# POWER2.net
KiCad netlist of a schematic drawn in Altium Designer
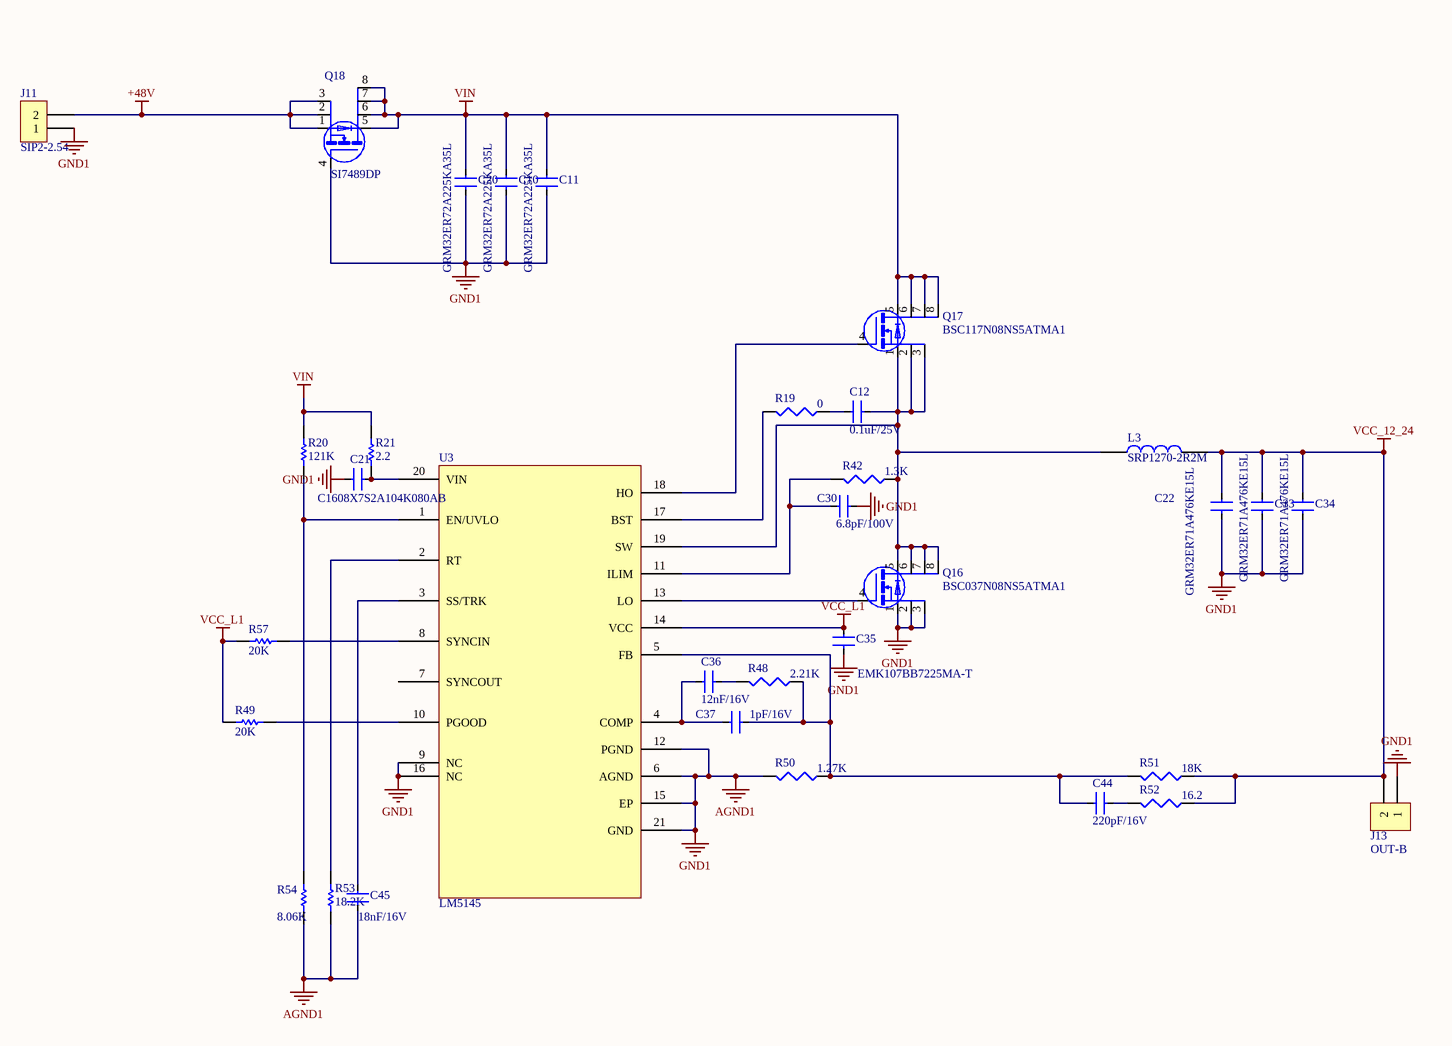
[diagram p0: POWER2.SchDoc]

(export (version "E")
  (design (tool "Eeschema 10.0.6"))
  (components
    (comp (ref "C10")
      (value "GRM32ER72A225KA35L")
      (footprint "1210C")
      (description "CCX85-103")
      (libsource (lib "无极性电容") (part "0.01UF"))
    )
    (comp (ref "C11")
      (value "GRM32ER72A225KA35L")
      (footprint "1210C")
      (description "CCX85-103")
      (libsource (lib "无极性电容") (part "0.01UF"))
    )
    (comp (ref "C12")
      (value "0.1uF/25V")
      (footprint "0603C")
      (description "CCX85-103")
      (libsource (lib "无极性电容") (part "0.01UF"))
    )
    (comp (ref "C20")
      (value "GRM32ER72A225KA35L")
      (footprint "1210C")
      (description "CCX85-103")
      (libsource (lib "无极性电容") (part "0.01UF"))
    )
    (comp (ref "C21")
      (value "C1608X7S2A104K080AB")
      (footprint "0603C")
      (description "CCX85-103")
      (libsource (lib "无极性电容") (part "0.01UF"))
    )
    (comp (ref "C22")
      (value "GRM32ER71A476KE15L")
      (footprint "1210C")
      (description "CCX85-103")
      (libsource (lib "无极性电容") (part "0.01UF"))
    )
    (comp (ref "C30")
      (value "6.8pF/100V")
      (footprint "0603C")
      (description "CCX85-103")
      (libsource (lib "无极性电容") (part "0.01UF"))
    )
    (comp (ref "C33")
      (value "GRM32ER71A476KE15L")
      (footprint "1210C")
      (description "CCX85-103")
      (libsource (lib "无极性电容") (part "0.01UF"))
    )
    (comp (ref "C34")
      (value "GRM32ER71A476KE15L")
      (footprint "1210C")
      (description "CCX85-103")
      (libsource (lib "无极性电容") (part "0.01UF"))
    )
    (comp (ref "C35")
      (value "EMK107BB7225MA-T")
      (footprint "0603C")
      (description "CCX85-103")
      (libsource (lib "无极性电容") (part "0.01UF"))
    )
    (comp (ref "C36")
      (value "12nF/16V")
      (footprint "0603C")
      (description "CCX85-103")
      (libsource (lib "无极性电容") (part "0.01UF"))
    )
    (comp (ref "C37")
      (value "1pF/16V")
      (footprint "0603C")
      (description "CCX85-103")
      (libsource (lib "无极性电容") (part "0.01UF"))
    )
    (comp (ref "C44")
      (value "220pF/16V")
      (footprint "0603C")
      (description "CCX85-103")
      (libsource (lib "无极性电容") (part "0.01UF"))
    )
    (comp (ref "C45")
      (value "18nF/16V")
      (footprint "0603C")
      (description "CCX85-103")
      (libsource (lib "无极性电容") (part "0.01UF"))
    )
    (comp (ref "J11")
      (value "SIP2-2.54")
      (footprint "CH3.96-2P")
      (description "CN-SIP2-2.54")
      (libsource (lib "接插件") (part "SIP2-2.54"))
    )
    (comp (ref "J13")
      (value "OUT-B")
      (footprint "CH3.96-2P")
      (description "Connector")
      (libsource (lib "SM") (part "CON2"))
    )
    (comp (ref "L3")
      (value "SRP1270-2R2M")
      (footprint "SRP1270-2R2M")
      (libsource (lib "*") (part "INDUCTOR"))
    )
    (comp (ref "Q16")
      (value "BSC037N08NS5ATMA1")
      (footprint "PowerPAK SO-8")
      (description "Si4004DY")
      (libsource (lib "Schlib_20110825") (part "Si4004DY"))
    )
    (comp (ref "Q17")
      (value "BSC117N08NS5ATMA1")
      (footprint "PowerPAK SO-8")
      (description "Si4004DY")
      (libsource (lib "Schlib_20110825") (part "Si4004DY"))
    )
    (comp (ref "Q18")
      (value "SI7489DP")
      (footprint "PowerPAK SO-8")
      (description "Si4004DY")
      (libsource (lib "") (part "Si4004DY_1"))
    )
    (comp (ref "R19")
      (value "0")
      (footprint "0603R")
      (description "Resistor")
      (fields (field (name "PUBLISHER") "Altium Limited"))
      (libsource (lib "SM") (part "Res3"))
    )
    (comp (ref "R20")
      (value "121K")
      (footprint "0805R")
      (description "Semiconductor Resistor")
      (fields (field (name "PUBLISHER") "Altium Limited"))
      (libsource (lib "Miscellaneous Devices") (part "Res Semi"))
    )
    (comp (ref "R21")
      (value "2.2")
      (footprint "0603R")
      (description "Semiconductor Resistor")
      (fields (field (name "PUBLISHER") "Altium Limited"))
      (libsource (lib "Miscellaneous Devices") (part "Res Semi"))
    )
    (comp (ref "R42")
      (value "1.3K")
      (footprint "0603R")
      (description "Resistor")
      (fields (field (name "PUBLISHER") "Altium Limited"))
      (libsource (lib "SM") (part "Res3"))
    )
    (comp (ref "R48")
      (value "2.21K")
      (footprint "0603R")
      (description "Resistor")
      (fields (field (name "PUBLISHER") "Altium Limited"))
      (libsource (lib "SM") (part "Res3"))
    )
    (comp (ref "R49")
      (value "20K")
      (footprint "0603R")
      (description "Semiconductor Resistor")
      (fields (field (name "PUBLISHER") "Altium Limited"))
      (libsource (lib "Miscellaneous Devices") (part "Res Semi"))
    )
    (comp (ref "R50")
      (value "1.27K")
      (footprint "0603R")
      (description "Resistor")
      (fields (field (name "PUBLISHER") "Altium Limited"))
      (libsource (lib "SM") (part "Res3"))
    )
    (comp (ref "R51")
      (value "18K")
      (footprint "0603R")
      (description "Resistor")
      (fields (field (name "PUBLISHER") "Altium Limited"))
      (libsource (lib "SM") (part "Res3"))
    )
    (comp (ref "R52")
      (value "16.2")
      (footprint "0603R")
      (description "Resistor")
      (fields (field (name "PUBLISHER") "Altium Limited"))
      (libsource (lib "SM") (part "Res3"))
    )
    (comp (ref "R53")
      (value "18.2K")
      (footprint "0603R")
      (description "Semiconductor Resistor")
      (fields (field (name "PUBLISHER") "Altium Limited"))
      (libsource (lib "Miscellaneous Devices") (part "Res Semi"))
    )
    (comp (ref "R54")
      (value "8.06K")
      (footprint "0603R")
      (description "Semiconductor Resistor")
      (fields (field (name "PUBLISHER") "Altium Limited"))
      (libsource (lib "Miscellaneous Devices") (part "Res Semi"))
    )
    (comp (ref "R57")
      (value "20K")
      (footprint "0603R")
      (description "Semiconductor Resistor")
      (fields (field (name "PUBLISHER") "Altium Limited"))
      (libsource (lib "Miscellaneous Devices") (part "Res Semi"))
    )
    (comp (ref "U3")
      (value "LM5145")
      (footprint "QFN050P600-8N")
      (libsource (lib "Schlib_20110825") (part "LM5145"))
    )
  )
  (nets
    (net (code "1") (name "+48V") (class "Default")
      (node (ref "J11") (pin "2") (pinfunction "2_2") (pintype "passive"))
      (node (ref "Q18") (pin "1") (pinfunction "S_1") (pintype "passive"))
      (node (ref "Q18") (pin "2") (pinfunction "S_2") (pintype "passive"))
      (node (ref "Q18") (pin "3") (pinfunction "S_3") (pintype "passive"))
    )
    (net (code "2") (name "AGND1") (class "Default")
      (node (ref "C10") (pin "2") (pinfunction "2_2") (pintype "passive"))
      (node (ref "C11") (pin "2") (pinfunction "2_2") (pintype "passive"))
      (node (ref "C20") (pin "2") (pinfunction "2_2") (pintype "passive"))
      (node (ref "C21") (pin "1") (pinfunction "1_1") (pintype "passive"))
      (node (ref "C22") (pin "2") (pinfunction "2_2") (pintype "passive"))
      (node (ref "C30") (pin "1") (pinfunction "1_1") (pintype "passive"))
      (node (ref "C33") (pin "2") (pinfunction "2_2") (pintype "passive"))
      (node (ref "C34") (pin "2") (pinfunction "2_2") (pintype "passive"))
      (node (ref "C35") (pin "2") (pinfunction "2_2") (pintype "passive"))
      (node (ref "C45") (pin "2") (pinfunction "2_2") (pintype "passive"))
      (node (ref "J11") (pin "1") (pinfunction "1_1") (pintype "passive"))
      (node (ref "J13") (pin "1") (pinfunction "1_1") (pintype "passive"))
      (node (ref "Q16") (pin "1") (pinfunction "S_1") (pintype "passive"))
      (node (ref "Q16") (pin "2") (pinfunction "S_2") (pintype "passive"))
      (node (ref "Q16") (pin "3") (pinfunction "S_3") (pintype "passive"))
      (node (ref "Q18") (pin "4") (pinfunction "G_4") (pintype "passive"))
      (node (ref "R50") (pin "2") (pinfunction "2_2") (pintype "passive"))
      (node (ref "R53") (pin "1") (pinfunction "1_1") (pintype "passive"))
      (node (ref "R54") (pin "1") (pinfunction "1_1") (pintype "passive"))
      (node (ref "U3") (pin "12") (pinfunction "PGND_12") (pintype "passive"))
      (node (ref "U3") (pin "15") (pinfunction "EP_15") (pintype "passive"))
      (node (ref "U3") (pin "16") (pinfunction "NC_16") (pintype "passive"))
      (node (ref "U3") (pin "21") (pinfunction "GND_21") (pintype "passive"))
      (node (ref "U3") (pin "6") (pinfunction "AGND_6") (pintype "passive"))
      (node (ref "U3") (pin "9") (pinfunction "NC_9") (pintype "passive"))
    )
    (net (code "3") (name "Net-(C12-Pad1)") (class "Default")
      (node (ref "C12") (pin "1") (pinfunction "1_1") (pintype "passive"))
      (node (ref "R19") (pin "1") (pinfunction "1_1") (pintype "passive"))
    )
    (net (code "4") (name "Net-(C36-Pad2)") (class "Default")
      (node (ref "C36") (pin "2") (pinfunction "2_2") (pintype "passive"))
      (node (ref "R48") (pin "2") (pinfunction "2_2") (pintype "passive"))
    )
    (net (code "5") (name "Net-(C44-Pad2)") (class "Default")
      (node (ref "C44") (pin "2") (pinfunction "2_2") (pintype "passive"))
      (node (ref "R52") (pin "2") (pinfunction "2_2") (pintype "passive"))
    )
    (net (code "6") (name "Net-(Q16-G)") (class "Default")
      (node (ref "Q16") (pin "4") (pinfunction "G_4") (pintype "passive"))
      (node (ref "U3") (pin "13") (pinfunction "LO_13") (pintype "passive"))
    )
    (net (code "7") (name "Net-(Q17-G)") (class "Default")
      (node (ref "Q17") (pin "4") (pinfunction "G_4") (pintype "passive"))
      (node (ref "U3") (pin "18") (pinfunction "HO_18") (pintype "passive"))
    )
    (net (code "8") (name "Net-(U3-BST)") (class "Default")
      (node (ref "R19") (pin "2") (pinfunction "2_2") (pintype "passive"))
      (node (ref "U3") (pin "17") (pinfunction "BST_17") (pintype "passive"))
    )
    (net (code "9") (name "Net-(U3-COMP)") (class "Default")
      (node (ref "C36") (pin "1") (pinfunction "1_1") (pintype "passive"))
      (node (ref "C37") (pin "1") (pinfunction "1_1") (pintype "passive"))
      (node (ref "U3") (pin "4") (pinfunction "COMP_4") (pintype "passive"))
    )
    (net (code "10") (name "Net-(U3-EN{slash}UVLO)") (class "Default")
      (node (ref "R20") (pin "1") (pinfunction "1_1") (pintype "passive"))
      (node (ref "R54") (pin "2") (pinfunction "2_2") (pintype "passive"))
      (node (ref "U3") (pin "1") (pinfunction "EN/UVLO_1") (pintype "passive"))
    )
    (net (code "11") (name "Net-(U3-FB)") (class "Default")
      (node (ref "C37") (pin "2") (pinfunction "2_2") (pintype "passive"))
      (node (ref "C44") (pin "1") (pinfunction "1_1") (pintype "passive"))
      (node (ref "R48") (pin "1") (pinfunction "1_1") (pintype "passive"))
      (node (ref "R50") (pin "1") (pinfunction "1_1") (pintype "passive"))
      (node (ref "R51") (pin "2") (pinfunction "2_2") (pintype "passive"))
      (node (ref "U3") (pin "5") (pinfunction "FB_5") (pintype "passive"))
    )
    (net (code "12") (name "Net-(U3-ILIM)") (class "Default")
      (node (ref "C30") (pin "2") (pinfunction "2_2") (pintype "passive"))
      (node (ref "R42") (pin "2") (pinfunction "2_2") (pintype "passive"))
      (node (ref "U3") (pin "11") (pinfunction "ILIM_11") (pintype "passive"))
    )
    (net (code "13") (name "Net-(U3-PGOOD)") (class "Default")
      (node (ref "R49") (pin "1") (pinfunction "1_1") (pintype "passive"))
      (node (ref "U3") (pin "10") (pinfunction "PGOOD_10") (pintype "passive"))
    )
    (net (code "14") (name "Net-(U3-RT)") (class "Default")
      (node (ref "R53") (pin "2") (pinfunction "2_2") (pintype "passive"))
      (node (ref "U3") (pin "2") (pinfunction "RT_2") (pintype "passive"))
    )
    (net (code "15") (name "Net-(U3-SS{slash}TRK)") (class "Default")
      (node (ref "C45") (pin "1") (pinfunction "1_1") (pintype "passive"))
      (node (ref "U3") (pin "3") (pinfunction "SS/TRK_3") (pintype "passive"))
    )
    (net (code "16") (name "Net-(U3-SW)") (class "Default")
      (node (ref "C12") (pin "2") (pinfunction "2_2") (pintype "passive"))
      (node (ref "L3") (pin "1") (pinfunction "1_1") (pintype "passive"))
      (node (ref "Q16") (pin "5") (pinfunction "D_5") (pintype "passive"))
      (node (ref "Q16") (pin "6") (pinfunction "D_6") (pintype "passive"))
      (node (ref "Q16") (pin "7") (pinfunction "D_7") (pintype "passive"))
      (node (ref "Q16") (pin "8") (pinfunction "D_8") (pintype "passive"))
      (node (ref "Q17") (pin "1") (pinfunction "S_1") (pintype "passive"))
      (node (ref "Q17") (pin "2") (pinfunction "S_2") (pintype "passive"))
      (node (ref "Q17") (pin "3") (pinfunction "S_3") (pintype "passive"))
      (node (ref "R42") (pin "1") (pinfunction "1_1") (pintype "passive"))
      (node (ref "U3") (pin "19") (pinfunction "SW_19") (pintype "passive"))
    )
    (net (code "17") (name "Net-(U3-SYNCIN)") (class "Default")
      (node (ref "R57") (pin "1") (pinfunction "1_1") (pintype "passive"))
      (node (ref "U3") (pin "8") (pinfunction "SYNCIN_8") (pintype "passive"))
    )
    (net (code "18") (name "Net-(U3-VIN)") (class "Default")
      (node (ref "C21") (pin "2") (pinfunction "2_2") (pintype "passive"))
      (node (ref "R21") (pin "2") (pinfunction "2_2") (pintype "passive"))
      (node (ref "U3") (pin "20") (pinfunction "VIN_20") (pintype "passive"))
    )
    (net (code "19") (name "VCC_12_24") (class "Default")
      (node (ref "C22") (pin "1") (pinfunction "1_1") (pintype "passive"))
      (node (ref "C33") (pin "1") (pinfunction "1_1") (pintype "passive"))
      (node (ref "C34") (pin "1") (pinfunction "1_1") (pintype "passive"))
      (node (ref "J13") (pin "2") (pinfunction "2_2") (pintype "passive"))
      (node (ref "L3") (pin "2") (pinfunction "2_2") (pintype "passive"))
      (node (ref "R51") (pin "1") (pinfunction "1_1") (pintype "passive"))
      (node (ref "R52") (pin "1") (pinfunction "1_1") (pintype "passive"))
    )
    (net (code "20") (name "VCC_L1") (class "Default")
      (node (ref "C35") (pin "1") (pinfunction "1_1") (pintype "passive"))
      (node (ref "R49") (pin "2") (pinfunction "2_2") (pintype "passive"))
      (node (ref "R57") (pin "2") (pinfunction "2_2") (pintype "passive"))
      (node (ref "U3") (pin "14") (pinfunction "VCC_14") (pintype "passive"))
    )
    (net (code "21") (name "VIN") (class "Default")
      (node (ref "C10") (pin "1") (pinfunction "1_1") (pintype "passive"))
      (node (ref "C11") (pin "1") (pinfunction "1_1") (pintype "passive"))
      (node (ref "C20") (pin "1") (pinfunction "1_1") (pintype "passive"))
      (node (ref "Q17") (pin "5") (pinfunction "D_5") (pintype "passive"))
      (node (ref "Q17") (pin "6") (pinfunction "D_6") (pintype "passive"))
      (node (ref "Q17") (pin "7") (pinfunction "D_7") (pintype "passive"))
      (node (ref "Q17") (pin "8") (pinfunction "D_8") (pintype "passive"))
      (node (ref "Q18") (pin "5") (pinfunction "D_5") (pintype "passive"))
      (node (ref "Q18") (pin "6") (pinfunction "D_6") (pintype "passive"))
      (node (ref "Q18") (pin "7") (pinfunction "D_7") (pintype "passive"))
      (node (ref "Q18") (pin "8") (pinfunction "D_8") (pintype "passive"))
      (node (ref "R20") (pin "2") (pinfunction "2_2") (pintype "passive"))
      (node (ref "R21") (pin "1") (pinfunction "1_1") (pintype "passive"))
    )
    (net (code "22") (name "unconnected-(U3-SYNCOUT-Pad7)") (class "Default")
      (node (ref "U3") (pin "7") (pinfunction "SYNCOUT_7") (pintype "passive"))
    )
  )
)
